# Ethernet2.net
KiCad netlist of a schematic drawn in Altium Designer
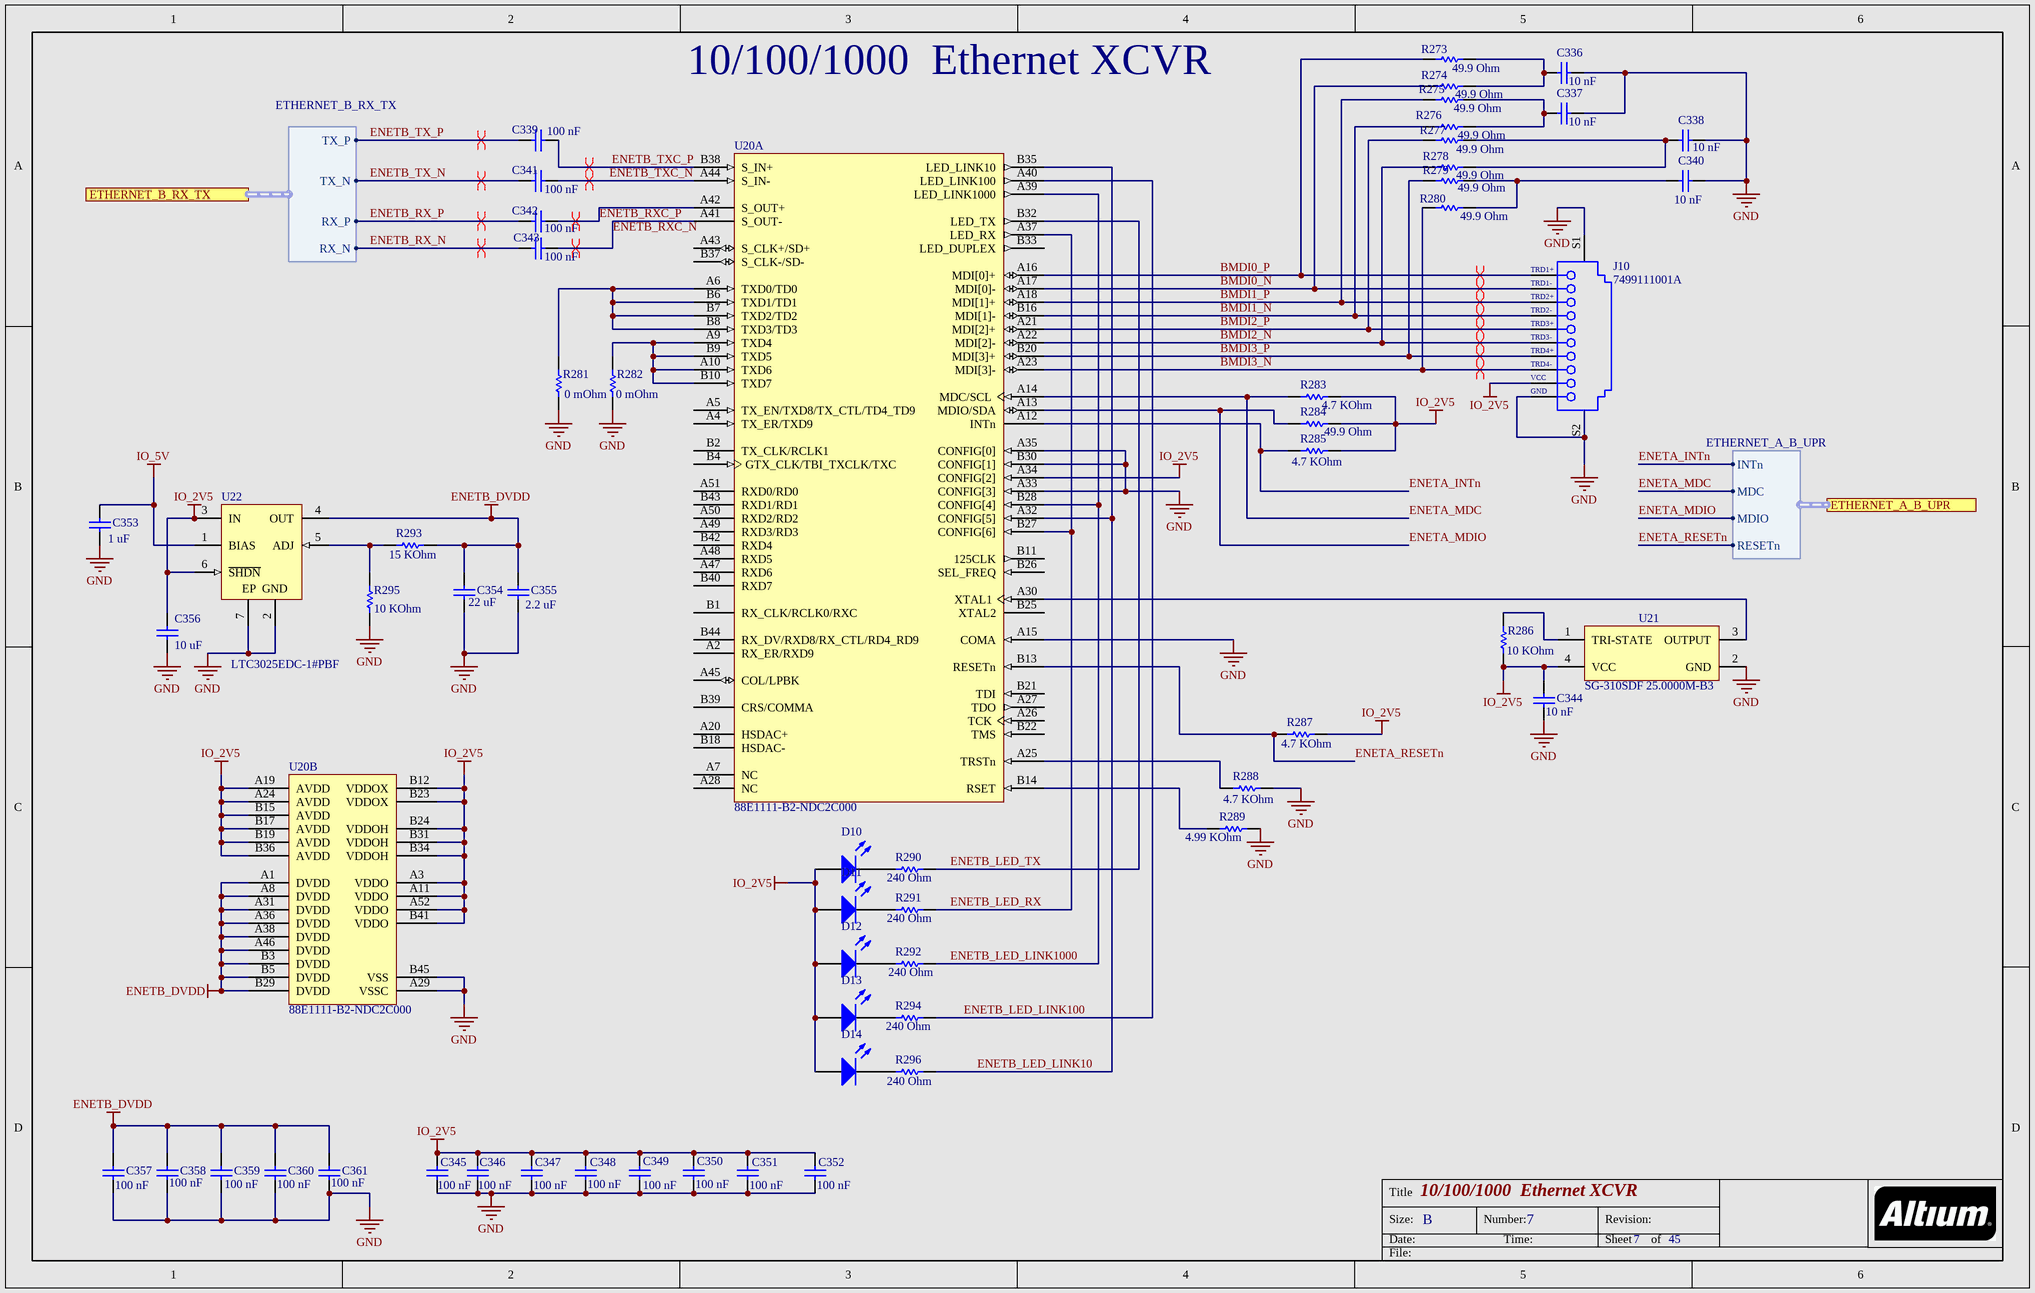
[diagram p0:  Ethernet2.SchDoc]

(export (version "E")
  (design (tool "Eeschema 10.0.6"))
  (components
    (comp (ref "C336")
      (value "GRM155R71H103KA88D")
      (footprint "CAPC1005X55X25ML05T10")
      (description "Chip Capacitor, 10 nF, +/- 10%, 50 V, -55 to 125 degC, 0402 (1005 Metric), RoHS, Tape and Reel")
      (fields
        (field (name "TOLERANCE") "10%")
        (field (name "CAPACITANCE") "10 nF")
        (field (name "MANUFACTURER") "Basic Passives")
      )
      (libsource (lib "Altium Content Vault") (part "CAP-NP-2"))
    )
    (comp (ref "C337")
      (value "GRM155R71H103KA88D")
      (footprint "CAPC1005X55X25ML05T10")
      (description "Chip Capacitor, 10 nF, +/- 10%, 50 V, -55 to 125 degC, 0402 (1005 Metric), RoHS, Tape and Reel")
      (fields
        (field (name "TOLERANCE") "10%")
        (field (name "CAPACITANCE") "10 nF")
        (field (name "MANUFACTURER") "Basic Passives")
      )
      (libsource (lib "Altium Content Vault") (part "CAP-NP-2"))
    )
    (comp (ref "C338")
      (value "GRM155R71H103KA88D")
      (footprint "CAPC1005X55X25ML05T10")
      (description "Chip Capacitor, 10 nF, +/- 10%, 50 V, -55 to 125 degC, 0402 (1005 Metric), RoHS, Tape and Reel")
      (fields
        (field (name "TOLERANCE") "10%")
        (field (name "CAPACITANCE") "10 nF")
        (field (name "MANUFACTURER") "Basic Passives")
      )
      (libsource (lib "Altium Content Vault") (part "CAP-NP-2"))
    )
    (comp (ref "C339")
      (value "C1005X7R1E104M")
      (footprint "CAPC1005X55X10LL05")
      (description "Chip Capacitor, 0.1 uF, +/- 20%, 25 V, -55 to 125 degC, 0402 (1005 Metric), RoHS, Tape and Reel")
      (fields (field (name "TOLERANCE") "20%") (field (name "CAPACITANCE") "100 nF"))
      (libsource (lib "Altium Content Vault") (part "CAP-NP-2"))
    )
    (comp (ref "C340")
      (value "GRM155R71H103KA88D")
      (footprint "CAPC1005X55X25ML05T10")
      (description "Chip Capacitor, 10 nF, +/- 10%, 50 V, -55 to 125 degC, 0402 (1005 Metric), RoHS, Tape and Reel")
      (fields
        (field (name "TOLERANCE") "10%")
        (field (name "CAPACITANCE") "10 nF")
        (field (name "MANUFACTURER") "Basic Passives")
      )
      (libsource (lib "Altium Content Vault") (part "CAP-NP-2"))
    )
    (comp (ref "C341")
      (value "C1005X7R1E104M")
      (footprint "CAPC1005X55X10LL05")
      (description "Chip Capacitor, 0.1 uF, +/- 20%, 25 V, -55 to 125 degC, 0402 (1005 Metric), RoHS, Tape and Reel")
      (fields (field (name "TOLERANCE") "20%") (field (name "CAPACITANCE") "100 nF"))
      (libsource (lib "Altium Content Vault") (part "CAP-NP-2"))
    )
    (comp (ref "C342")
      (value "C1005X7R1E104M")
      (footprint "CAPC1005X55X10LL05")
      (description "Chip Capacitor, 0.1 uF, +/- 20%, 25 V, -55 to 125 degC, 0402 (1005 Metric), RoHS, Tape and Reel")
      (fields (field (name "TOLERANCE") "20%") (field (name "CAPACITANCE") "100 nF"))
      (libsource (lib "Altium Content Vault") (part "CAP-NP-2"))
    )
    (comp (ref "C343")
      (value "C1005X7R1E104M")
      (footprint "CAPC1005X55X10LL05")
      (description "Chip Capacitor, 0.1 uF, +/- 20%, 25 V, -55 to 125 degC, 0402 (1005 Metric), RoHS, Tape and Reel")
      (fields (field (name "TOLERANCE") "20%") (field (name "CAPACITANCE") "100 nF"))
      (libsource (lib "Altium Content Vault") (part "CAP-NP-2"))
    )
    (comp (ref "C344")
      (value "GRM155R71H103KA88D")
      (footprint "CAPC1005X55X25ML05T10")
      (description "Chip Capacitor, 10 nF, +/- 10%, 50 V, -55 to 125 degC, 0402 (1005 Metric), RoHS, Tape and Reel")
      (fields
        (field (name "TOLERANCE") "10%")
        (field (name "CAPACITANCE") "10 nF")
        (field (name "MANUFACTURER") "Basic Passives")
      )
      (libsource (lib "Altium Content Vault") (part "CAP-NP-2"))
    )
    (comp (ref "C345")
      (value "C1005X7R1E104M")
      (footprint "CAPC1005X55X10LL05")
      (description "Chip Capacitor, 0.1 uF, +/- 20%, 25 V, -55 to 125 degC, 0402 (1005 Metric), RoHS, Tape and Reel")
      (fields (field (name "TOLERANCE") "20%") (field (name "CAPACITANCE") "100 nF"))
      (libsource (lib "Altium Content Vault") (part "CAP-NP-2"))
    )
    (comp (ref "C346")
      (value "C1005X7R1E104M")
      (footprint "CAPC1005X55X10LL05")
      (description "Chip Capacitor, 0.1 uF, +/- 20%, 25 V, -55 to 125 degC, 0402 (1005 Metric), RoHS, Tape and Reel")
      (fields (field (name "TOLERANCE") "20%") (field (name "CAPACITANCE") "100 nF"))
      (libsource (lib "Altium Content Vault") (part "CAP-NP-2"))
    )
    (comp (ref "C347")
      (value "C1005X7R1E104M")
      (footprint "CAPC1005X55X10LL05")
      (description "Chip Capacitor, 0.1 uF, +/- 20%, 25 V, -55 to 125 degC, 0402 (1005 Metric), RoHS, Tape and Reel")
      (fields (field (name "TOLERANCE") "20%") (field (name "CAPACITANCE") "100 nF"))
      (libsource (lib "Altium Content Vault") (part "CAP-NP-2"))
    )
    (comp (ref "C348")
      (value "C1005X7R1E104M")
      (footprint "CAPC1005X55X10LL05")
      (description "Chip Capacitor, 0.1 uF, +/- 20%, 25 V, -55 to 125 degC, 0402 (1005 Metric), RoHS, Tape and Reel")
      (fields (field (name "TOLERANCE") "20%") (field (name "CAPACITANCE") "100 nF"))
      (libsource (lib "Altium Content Vault") (part "CAP-NP-2"))
    )
    (comp (ref "C349")
      (value "C1005X7R1E104M")
      (footprint "CAPC1005X55X10LL05")
      (description "Chip Capacitor, 0.1 uF, +/- 20%, 25 V, -55 to 125 degC, 0402 (1005 Metric), RoHS, Tape and Reel")
      (fields (field (name "TOLERANCE") "20%") (field (name "CAPACITANCE") "100 nF"))
      (libsource (lib "Altium Content Vault") (part "CAP-NP-2"))
    )
    (comp (ref "C350")
      (value "C1005X7R1E104M")
      (footprint "CAPC1005X55X10LL05")
      (description "Chip Capacitor, 0.1 uF, +/- 20%, 25 V, -55 to 125 degC, 0402 (1005 Metric), RoHS, Tape and Reel")
      (fields (field (name "TOLERANCE") "20%") (field (name "CAPACITANCE") "100 nF"))
      (libsource (lib "Altium Content Vault") (part "CAP-NP-2"))
    )
    (comp (ref "C351")
      (value "C1005X7R1E104M")
      (footprint "CAPC1005X55X10LL05")
      (description "Chip Capacitor, 0.1 uF, +/- 20%, 25 V, -55 to 125 degC, 0402 (1005 Metric), RoHS, Tape and Reel")
      (fields (field (name "TOLERANCE") "20%") (field (name "CAPACITANCE") "100 nF"))
      (libsource (lib "Altium Content Vault") (part "CAP-NP-2"))
    )
    (comp (ref "C352")
      (value "C1005X7R1E104M")
      (footprint "CAPC1005X55X10LL05")
      (description "Chip Capacitor, 0.1 uF, +/- 20%, 25 V, -55 to 125 degC, 0402 (1005 Metric), RoHS, Tape and Reel")
      (fields (field (name "TOLERANCE") "20%") (field (name "CAPACITANCE") "100 nF"))
      (libsource (lib "Altium Content Vault") (part "CAP-NP-2"))
    )
    (comp (ref "C353")
      (value "CGB2A1X5R1E105K033BC")
      (footprint "CAPC1005X33X10LL5")
      (description "Chip Capacitor, 1 uF, +/- 10%, 25 V, -55 to 85 degC, 0402 (1005 Metric), RoHS, Tape and Reel")
      (fields (field (name "CAPACITANCE") "1 uF") (field (name "TOLERANCE") "10%"))
      (libsource (lib "") (part "CAP-NP-2_1"))
    )
    (comp (ref "C354")
      (value "GRM31CR61E226KE15L")
      (footprint "CAPC3216X180X55ML20T25")
      (description "Chip Capacitor, 22 uF, +/- 10%, 25 V, -55 to 85 degC, 1206 (3216 Metric), RoHS, Tape and Reel")
      (fields (field (name "TOLERANCE") "10%") (field (name "CAPACITANCE") "22 uF"))
      (libsource (lib "Altium Content Vault") (part "CAP-NP-2"))
    )
    (comp (ref "C355")
      (value "GRM188R61A225KE34x")
      (footprint "CAPC1608X90X35ML10T15")
      (description "Chip Capacitor, 2.2 uF, +/- 10%, 10 V, -55 to 85 degC, 0603 (1608 Metric), RoHS, Tape and Reel")
      (fields (field (name "TOLERANCE") "10%") (field (name "CAPACITANCE") "2.2 uF"))
      (libsource (lib "") (part "CAP-NP-2_1"))
    )
    (comp (ref "C356")
      (value "C2012X5R1C106K085AC")
      (footprint "CAPC2013X100X20NL20")
      (description "Chip Capacitor, 10 uF, +/- 10%, 16 V, -55 to 85 degC, 0805 (2012 Metric), RoHS, Tape and Reel")
      (fields (field (name "TOLERANCE") "10%") (field (name "CAPACITANCE") "10 uF"))
      (libsource (lib "") (part "CAP-NP-2_1"))
    )
    (comp (ref "C357")
      (value "C1005X7R1E104M")
      (footprint "CAPC1005X55X10LL05")
      (description "Chip Capacitor, 0.1 uF, +/- 20%, 25 V, -55 to 125 degC, 0402 (1005 Metric), RoHS, Tape and Reel")
      (fields (field (name "TOLERANCE") "20%") (field (name "CAPACITANCE") "100 nF"))
      (libsource (lib "Altium Content Vault") (part "CAP-NP-2"))
    )
    (comp (ref "C358")
      (value "C1005X7R1E104M")
      (footprint "CAPC1005X55X10LL05")
      (description "Chip Capacitor, 0.1 uF, +/- 20%, 25 V, -55 to 125 degC, 0402 (1005 Metric), RoHS, Tape and Reel")
      (fields (field (name "TOLERANCE") "20%") (field (name "CAPACITANCE") "100 nF"))
      (libsource (lib "Altium Content Vault") (part "CAP-NP-2"))
    )
    (comp (ref "C359")
      (value "C1005X7R1E104M")
      (footprint "CAPC1005X55X10LL05")
      (description "Chip Capacitor, 0.1 uF, +/- 20%, 25 V, -55 to 125 degC, 0402 (1005 Metric), RoHS, Tape and Reel")
      (fields (field (name "TOLERANCE") "20%") (field (name "CAPACITANCE") "100 nF"))
      (libsource (lib "Altium Content Vault") (part "CAP-NP-2"))
    )
    (comp (ref "C360")
      (value "C1005X7R1E104M")
      (footprint "CAPC1005X55X10LL05")
      (description "Chip Capacitor, 0.1 uF, +/- 20%, 25 V, -55 to 125 degC, 0402 (1005 Metric), RoHS, Tape and Reel")
      (fields (field (name "TOLERANCE") "20%") (field (name "CAPACITANCE") "100 nF"))
      (libsource (lib "Altium Content Vault") (part "CAP-NP-2"))
    )
    (comp (ref "C361")
      (value "C1005X7R1E104M")
      (footprint "CAPC1005X55X10LL05")
      (description "Chip Capacitor, 0.1 uF, +/- 20%, 25 V, -55 to 125 degC, 0402 (1005 Metric), RoHS, Tape and Reel")
      (fields (field (name "TOLERANCE") "20%") (field (name "CAPACITANCE") "100 nF"))
      (libsource (lib "Altium Content Vault") (part "CAP-NP-2"))
    )
    (comp (ref "D10")
      (value "150060VS75000")
      (footprint "0603_A")
      (description "SMD mono-color Chip LED, WL-SMCW, Bright Green")
      (fields (field (name "MANUFACTURER") "Wuerth Elektronik"))
      (libsource (lib "Altium Content Vault") (part "CMP-1426-00006-1"))
    )
    (comp (ref "D11")
      (value "150060VS75000")
      (footprint "0603_A")
      (description "SMD mono-color Chip LED, WL-SMCW, Bright Green")
      (fields (field (name "MANUFACTURER") "Wuerth Elektronik"))
      (libsource (lib "Altium Content Vault") (part "CMP-1426-00006-1"))
    )
    (comp (ref "D12")
      (value "150060VS75000")
      (footprint "0603_A")
      (description "SMD mono-color Chip LED, WL-SMCW, Bright Green")
      (fields (field (name "MANUFACTURER") "Wuerth Elektronik"))
      (libsource (lib "Altium Content Vault") (part "CMP-1426-00006-1"))
    )
    (comp (ref "D13")
      (value "150060VS75000")
      (footprint "0603_A")
      (description "SMD mono-color Chip LED, WL-SMCW, Bright Green")
      (fields (field (name "MANUFACTURER") "Wuerth Elektronik"))
      (libsource (lib "Altium Content Vault") (part "CMP-1426-00006-1"))
    )
    (comp (ref "D14")
      (value "150060VS75000")
      (footprint "0603_A")
      (description "SMD mono-color Chip LED, WL-SMCW, Bright Green")
      (fields (field (name "MANUFACTURER") "Wuerth Elektronik"))
      (libsource (lib "Altium Content Vault") (part "CMP-1426-00006-1"))
    )
    (comp (ref "J10")
      (value "7499111001A")
      (footprint "WE-7499111001A_V")
      (description "RJ45 LAN Transformer, Modular JACK, 0 to 70 degC, 10-Pin THD, RoHS, Tube")
      (libsource (lib "Altium Content Vault") (part "RJ45-10-2SHLD_A"))
    )
    (comp (ref "R273")
      (value "NRC04F49R9TRF")
      (footprint "RESC1005X35X25NL8T10")
      (description "Chip Resistor, 49.9 Ohm, +/- 1%, 0.06 W, -55 to 155 degC, 0402 (1005 Metric), RoHS, Tape and Reel")
      (fields (field (name "TOLERANCE") "1%") (field (name "RESISTANCE") "49.9 Ohm"))
      (libsource (lib "Altium Content Vault") (part "CMP-1599-00001-2"))
    )
    (comp (ref "R274")
      (value "NRC04F49R9TRF")
      (footprint "RESC1005X35X25NL8T10")
      (description "Chip Resistor, 49.9 Ohm, +/- 1%, 0.06 W, -55 to 155 degC, 0402 (1005 Metric), RoHS, Tape and Reel")
      (fields (field (name "TOLERANCE") "1%") (field (name "RESISTANCE") "49.9 Ohm"))
      (libsource (lib "Altium Content Vault") (part "RES-2"))
    )
    (comp (ref "R275")
      (value "NRC04F49R9TRF")
      (footprint "RESC1005X35X25NL8T10")
      (description "Chip Resistor, 49.9 Ohm, +/- 1%, 0.06 W, -55 to 155 degC, 0402 (1005 Metric), RoHS, Tape and Reel")
      (fields (field (name "TOLERANCE") "1%") (field (name "RESISTANCE") "49.9 Ohm"))
      (libsource (lib "Altium Content Vault") (part "RES-2"))
    )
    (comp (ref "R276")
      (value "NRC04F49R9TRF")
      (footprint "RESC1005X35X25NL8T10")
      (description "Chip Resistor, 49.9 Ohm, +/- 1%, 0.06 W, -55 to 155 degC, 0402 (1005 Metric), RoHS, Tape and Reel")
      (fields (field (name "TOLERANCE") "1%") (field (name "RESISTANCE") "49.9 Ohm"))
      (libsource (lib "Altium Content Vault") (part "CMP-1599-00001-2"))
    )
    (comp (ref "R277")
      (value "NRC04F49R9TRF")
      (footprint "RESC1005X35X25NL8T10")
      (description "Chip Resistor, 49.9 Ohm, +/- 1%, 0.06 W, -55 to 155 degC, 0402 (1005 Metric), RoHS, Tape and Reel")
      (fields (field (name "TOLERANCE") "1%") (field (name "RESISTANCE") "49.9 Ohm"))
      (libsource (lib "Altium Content Vault") (part "RES-2"))
    )
    (comp (ref "R278")
      (value "NRC04F49R9TRF")
      (footprint "RESC1005X35X25NL8T10")
      (description "Chip Resistor, 49.9 Ohm, +/- 1%, 0.06 W, -55 to 155 degC, 0402 (1005 Metric), RoHS, Tape and Reel")
      (fields (field (name "TOLERANCE") "1%") (field (name "RESISTANCE") "49.9 Ohm"))
      (libsource (lib "Altium Content Vault") (part "RES-2"))
    )
    (comp (ref "R279")
      (value "NRC04F49R9TRF")
      (footprint "RESC1005X35X25NL8T10")
      (description "Chip Resistor, 49.9 Ohm, +/- 1%, 0.06 W, -55 to 155 degC, 0402 (1005 Metric), RoHS, Tape and Reel")
      (fields (field (name "TOLERANCE") "1%") (field (name "RESISTANCE") "49.9 Ohm"))
      (libsource (lib "Altium Content Vault") (part "CMP-1599-00001-2"))
    )
    (comp (ref "R280")
      (value "NRC04F49R9TRF")
      (footprint "RESC1005X35X25NL8T10")
      (description "Chip Resistor, 49.9 Ohm, +/- 1%, 0.06 W, -55 to 155 degC, 0402 (1005 Metric), RoHS, Tape and Reel")
      (fields (field (name "TOLERANCE") "1%") (field (name "RESISTANCE") "49.9 Ohm"))
      (libsource (lib "Altium Content Vault") (part "RES-2"))
    )
    (comp (ref "R281")
      (value "ERJ-2GE0R00X")
      (footprint "RESC1005X40X25ML05T05")
      (description "Chip Resistor, 0 mOhm, +/- 5%, 100 mW, -55 to 155 degC, 0402 (1005 Metric), RoHS, Tape and Reel")
      (fields
        (field (name "TOLERANCE") "5%")
        (field (name "RESISTANCE") "0 mOhm")
        (field (name "MANUFACTURER") "Basic Passives")
      )
      (libsource (lib "Altium Content Vault") (part "RES-2"))
    )
    (comp (ref "R282")
      (value "ERJ-2GE0R00X")
      (footprint "RESC1005X40X25ML05T05")
      (description "Chip Resistor, 0 mOhm, +/- 5%, 100 mW, -55 to 155 degC, 0402 (1005 Metric), RoHS, Tape and Reel")
      (fields
        (field (name "TOLERANCE") "5%")
        (field (name "RESISTANCE") "0 mOhm")
        (field (name "MANUFACTURER") "Basic Passives")
      )
      (libsource (lib "Altium Content Vault") (part "RES-2"))
    )
    (comp (ref "R283")
      (value "ERJ-2RKF4701X")
      (footprint "RESC1005X40X25LL05T05")
      (description "Chip Resistor, 4.7 KOhm, +/- 1%, 0.1 W, -55 to 155 degC, 0402 (1005 Metric), RoHS, Tape and Reel")
      (fields (field (name "TOLERANCE") "1%") (field (name "RESISTANCE") "4.7 KOhm"))
      (libsource (lib "Altium Content Vault") (part "RES-2"))
    )
    (comp (ref "R284")
      (value "NRC04F49R9TRF")
      (footprint "RESC1005X35X25NL8T10")
      (description "Chip Resistor, 49.9 Ohm, +/- 1%, 0.06 W, -55 to 155 degC, 0402 (1005 Metric), RoHS, Tape and Reel")
      (fields (field (name "TOLERANCE") "1%") (field (name "RESISTANCE") "49.9 Ohm"))
      (libsource (lib "Altium Content Vault") (part "CMP-1599-00001-2"))
    )
    (comp (ref "R285")
      (value "ERJ-2RKF4701X")
      (footprint "RESC1005X40X25LL05T05")
      (description "Chip Resistor, 4.7 KOhm, +/- 1%, 0.1 W, -55 to 155 degC, 0402 (1005 Metric), RoHS, Tape and Reel")
      (fields (field (name "TOLERANCE") "1%") (field (name "RESISTANCE") "4.7 KOhm"))
      (libsource (lib "Altium Content Vault") (part "RES-2"))
    )
    (comp (ref "R286")
      (value "ERJ-2RKF1002X")
      (footprint "RESC1005X40X25NL05T05")
      (description "Chip Resistor, 10 KOhm, +/- 1%, 100 mW, -55 to 155 degC, 0402 (1005 Metric), RoHS, Tape and Reel")
      (fields
        (field (name "TOLERANCE") "1%")
        (field (name "RESISTANCE") "10 KOhm")
        (field (name "MANUFACTURER") "Basic Passives")
      )
      (libsource (lib "Altium Content Vault") (part "RES-2"))
    )
    (comp (ref "R287")
      (value "ERJ-2RKF4701X")
      (footprint "RESC1005X40X25LL05T05")
      (description "Chip Resistor, 4.7 KOhm, +/- 1%, 0.1 W, -55 to 155 degC, 0402 (1005 Metric), RoHS, Tape and Reel")
      (fields (field (name "TOLERANCE") "1%") (field (name "RESISTANCE") "4.7 KOhm"))
      (libsource (lib "Altium Content Vault") (part "RES-2"))
    )
    (comp (ref "R288")
      (value "ERJ-2RKF4701X")
      (footprint "RESC1005X40X25LL05T05")
      (description "Chip Resistor, 4.7 KOhm, +/- 1%, 0.1 W, -55 to 155 degC, 0402 (1005 Metric), RoHS, Tape and Reel")
      (fields (field (name "TOLERANCE") "1%") (field (name "RESISTANCE") "4.7 KOhm"))
      (libsource (lib "Altium Content Vault") (part "RES-2"))
    )
    (comp (ref "R289")
      (value "ERJ-2RKF4991X")
      (footprint "RESC1005X40X25NL05T05")
      (description "Chip Resistor, 4.99 KOhm, +/- 1%, 100 mW, -55 to 155 degC, 0402 (1005 Metric), RoHS, Tape and Reel")
      (fields
        (field (name "TOLERANCE") "1%")
        (field (name "RESISTANCE") "4.99 KOhm")
        (field (name "MANUFACTURER") "Basic Passives")
      )
      (libsource (lib "Altium Content Vault") (part "RES-2"))
    )
    (comp (ref "R290")
      (value "ERJ-2RKF2400X")
      (footprint "RESC1005X40X25NL05T05")
      (description "Chip Resistor, 240 Ohm, +/- 1%, 100 mW, -55 to 155 degC, 0402 (1005 Metric), RoHS, Tape and Reel")
      (fields (field (name "TOLERANCE") "1%") (field (name "RESISTANCE") "240 Ohm"))
      (libsource (lib "Altium Content Vault") (part "RES-2"))
    )
    (comp (ref "R291")
      (value "ERJ-2RKF2400X")
      (footprint "RESC1005X40X25NL05T05")
      (description "Chip Resistor, 240 Ohm, +/- 1%, 100 mW, -55 to 155 degC, 0402 (1005 Metric), RoHS, Tape and Reel")
      (fields (field (name "TOLERANCE") "1%") (field (name "RESISTANCE") "240 Ohm"))
      (libsource (lib "Altium Content Vault") (part "RES-2"))
    )
    (comp (ref "R292")
      (value "ERJ-2RKF2400X")
      (footprint "RESC1005X40X25NL05T05")
      (description "Chip Resistor, 240 Ohm, +/- 1%, 100 mW, -55 to 155 degC, 0402 (1005 Metric), RoHS, Tape and Reel")
      (fields (field (name "TOLERANCE") "1%") (field (name "RESISTANCE") "240 Ohm"))
      (libsource (lib "Altium Content Vault") (part "RES-2"))
    )
    (comp (ref "R293")
      (value "ERJ-2RKF1502X")
      (footprint "RESC1005X40X25ML05T05")
      (description "Chip Resistor, 15 KOhm, +/- 1%, 100 mW, -55 to 155 degC, 0402 (1005 Metric), RoHS, Tape and Reel")
      (fields
        (field (name "RESISTANCE") "15 KOhm")
        (field (name "TOLERANCE") "1%")
        (field (name "MANUFACTURER") "Basic Passives")
      )
      (libsource (lib "Altium Content Vault") (part "RES-2"))
    )
    (comp (ref "R294")
      (value "ERJ-2RKF2400X")
      (footprint "RESC1005X40X25NL05T05")
      (description "Chip Resistor, 240 Ohm, +/- 1%, 100 mW, -55 to 155 degC, 0402 (1005 Metric), RoHS, Tape and Reel")
      (fields (field (name "TOLERANCE") "1%") (field (name "RESISTANCE") "240 Ohm"))
      (libsource (lib "Altium Content Vault") (part "RES-2"))
    )
    (comp (ref "R295")
      (value "ERJ-2RKF1002X")
      (footprint "RESC1005X40X25NL05T05")
      (description "Chip Resistor, 10 KOhm, +/- 1%, 100 mW, -55 to 155 degC, 0402 (1005 Metric), RoHS, Tape and Reel")
      (fields
        (field (name "TOLERANCE") "1%")
        (field (name "RESISTANCE") "10 KOhm")
        (field (name "MANUFACTURER") "Basic Passives")
      )
      (libsource (lib "Altium Content Vault") (part "RES-2"))
    )
    (comp (ref "R296")
      (value "ERJ-2RKF2400X")
      (footprint "RESC1005X40X25NL05T05")
      (description "Chip Resistor, 240 Ohm, +/- 1%, 100 mW, -55 to 155 degC, 0402 (1005 Metric), RoHS, Tape and Reel")
      (fields (field (name "TOLERANCE") "1%") (field (name "RESISTANCE") "240 Ohm"))
      (libsource (lib "Altium Content Vault") (part "RES-2"))
    )
    (comp (ref "U20")
      (value "88E1111-B2-NDC2C000")
      (footprint "MARV-NDC96")
      (description "Integrated 10/100/1000 Ultra Gigabit Ethernet Transceiver, Commercial Grade, 96-Pin QFN, RoHS")
      (libsource (lib "Altium Content Vault") (part "MARV-88E1111-NDC96"))
    )
    (comp (ref "U21")
      (value "SG-310SDF 25.0000M-B3")
      (footprint "EPSON-SG-310-4_V")
      (description "Crystal Oscillator (SPXO), 2.5 V, 25 MHz, -20 to 70 degC, 4-Pin SMD, RoHS, Tape and Reel")
      (libsource (lib "Altium Content Vault") (part "XTAL-1-3-4_B"))
    )
    (comp (ref "U22")
      (value "LTC3025EDC-1#PBF")
      (footprint "LT-DC6-6_V")
      (fields (field (name "MANUFACTURER") "Linear Technology"))
      (libsource (lib "Altium Content Vault") (part "LT-LTC302-DC6-6"))
    )
  )
  (nets
    (net (code "3") (name "/BMDI0_N") (class "Default")
      (node (ref "J10") (pin "2") (pinfunction "TRD1-_2") (pintype "passive"))
      (node (ref "R274") (pin "1") (pinfunction "1_1") (pintype "passive"))
      (node (ref "U20") (pin "A17") (pinfunction "MDI[0]-_A17") (pintype "bidirectional"))
    )
    (net (code "4") (name "/BMDI0_P") (class "Default")
      (node (ref "J10") (pin "1") (pinfunction "TRD1+_1") (pintype "passive"))
      (node (ref "R273") (pin "1") (pinfunction "1_1") (pintype "passive"))
      (node (ref "U20") (pin "A16") (pinfunction "MDI[0]+_A16") (pintype "bidirectional"))
    )
    (net (code "5") (name "/BMDI1_N") (class "Default")
      (node (ref "J10") (pin "4") (pinfunction "TRD2-_4") (pintype "passive"))
      (node (ref "R276") (pin "1") (pinfunction "1_1") (pintype "passive"))
      (node (ref "U20") (pin "B16") (pinfunction "MDI[1]-_B16") (pintype "bidirectional"))
    )
    (net (code "6") (name "/BMDI1_P") (class "Default")
      (node (ref "J10") (pin "3") (pinfunction "TRD2+_3") (pintype "passive"))
      (node (ref "R275") (pin "1") (pinfunction "1_1") (pintype "passive"))
      (node (ref "U20") (pin "A18") (pinfunction "MDI[1]+_A18") (pintype "bidirectional"))
    )
    (net (code "7") (name "/BMDI2_N") (class "Default")
      (node (ref "J10") (pin "6") (pinfunction "TRD3-_6") (pintype "passive"))
      (node (ref "R278") (pin "1") (pinfunction "1_1") (pintype "passive"))
      (node (ref "U20") (pin "A22") (pinfunction "MDI[2]-_A22") (pintype "bidirectional"))
    )
    (net (code "8") (name "/BMDI2_P") (class "Default")
      (node (ref "J10") (pin "5") (pinfunction "TRD3+_5") (pintype "passive"))
      (node (ref "R277") (pin "1") (pinfunction "1_1") (pintype "passive"))
      (node (ref "U20") (pin "A21") (pinfunction "MDI[2]+_A21") (pintype "bidirectional"))
    )
    (net (code "9") (name "/BMDI3_N") (class "Default")
      (node (ref "J10") (pin "8") (pinfunction "TRD4-_8") (pintype "passive"))
      (node (ref "R280") (pin "1") (pinfunction "1_1") (pintype "passive"))
      (node (ref "U20") (pin "A23") (pinfunction "MDI[3]-_A23") (pintype "bidirectional"))
    )
    (net (code "10") (name "/BMDI3_P") (class "Default")
      (node (ref "J10") (pin "7") (pinfunction "TRD4+_7") (pintype "passive"))
      (node (ref "R279") (pin "1") (pinfunction "1_1") (pintype "passive"))
      (node (ref "U20") (pin "B20") (pinfunction "MDI[3]+_B20") (pintype "bidirectional"))
    )
    (net (code "11") (name "/ENETA_INTn") (class "Default")
      (node (ref "R285") (pin "1") (pinfunction "1_1") (pintype "passive"))
      (node (ref "U20") (pin "A12") (pinfunction "INTn_A12") (pintype "passive"))
    )
    (net (code "12") (name "/ENETA_MDC") (class "Default")
      (node (ref "R283") (pin "1") (pinfunction "1_1") (pintype "passive"))
      (node (ref "U20") (pin "A14") (pinfunction "MDC/SCL_A14") (pintype "input"))
    )
    (net (code "13") (name "/ENETA_MDIO") (class "Default")
      (node (ref "R284") (pin "1") (pinfunction "1_1") (pintype "passive"))
      (node (ref "U20") (pin "A13") (pinfunction "MDIO/SDA_A13") (pintype "bidirectional"))
    )
    (net (code "14") (name "/ENETA_RESETn") (class "Default")
      (node (ref "R287") (pin "1") (pinfunction "1_1") (pintype "passive"))
      (node (ref "U20") (pin "B13") (pinfunction "RESETn_B13") (pintype "input"))
    )
    (net (code "15") (name "/ENETB_LED_LINK10") (class "Default")
      (node (ref "R296") (pin "2") (pinfunction "2_2") (pintype "passive"))
      (node (ref "U20") (pin "A32") (pinfunction "CONFIG[5]_A32") (pintype "input"))
      (node (ref "U20") (pin "B35") (pinfunction "LED_LINK10_B35") (pintype "output"))
    )
    (net (code "16") (name "/ENETB_LED_LINK100") (class "Default")
      (node (ref "R294") (pin "2") (pinfunction "2_2") (pintype "passive"))
      (node (ref "U20") (pin "A40") (pinfunction "LED_LINK100_A40") (pintype "output"))
    )
    (net (code "17") (name "/ENETB_LED_LINK1000") (class "Default")
      (node (ref "R292") (pin "2") (pinfunction "2_2") (pintype "passive"))
      (node (ref "U20") (pin "A39") (pinfunction "LED_LINK1000_A39") (pintype "output"))
      (node (ref "U20") (pin "B28") (pinfunction "CONFIG[4]_B28") (pintype "input"))
    )
    (net (code "18") (name "/ENETB_LED_RX") (class "Default")
      (node (ref "R291") (pin "2") (pinfunction "2_2") (pintype "passive"))
      (node (ref "U20") (pin "A37") (pinfunction "LED_RX_A37") (pintype "output"))
      (node (ref "U20") (pin "B27") (pinfunction "CONFIG[6]_B27") (pintype "input"))
    )
    (net (code "19") (name "/ENETB_LED_TX") (class "Default")
      (node (ref "R290") (pin "2") (pinfunction "2_2") (pintype "passive"))
      (node (ref "U20") (pin "B32") (pinfunction "LED_TX_B32") (pintype "output"))
    )
    (net (code "20") (name "/ENETB_RXC_N") (class "Default")
      (node (ref "C343") (pin "2") (pinfunction "2_2") (pintype "passive"))
      (node (ref "U20") (pin "A41") (pinfunction "S_OUT-_A41") (pintype "tri_state"))
    )
    (net (code "21") (name "/ENETB_RXC_P") (class "Default")
      (node (ref "C342") (pin "2") (pinfunction "2_2") (pintype "passive"))
      (node (ref "U20") (pin "A42") (pinfunction "S_OUT+_A42") (pintype "tri_state"))
    )
    (net (code "22") (name "/ENETB_RX_N") (class "Default")
      (node (ref "C343") (pin "1") (pinfunction "1_1") (pintype "passive"))
    )
    (net (code "23") (name "/ENETB_RX_P") (class "Default")
      (node (ref "C342") (pin "1") (pinfunction "1_1") (pintype "passive"))
    )
    (net (code "24") (name "/ENETB_TXC_N") (class "Default")
      (node (ref "C341") (pin "2") (pinfunction "2_2") (pintype "passive"))
      (node (ref "U20") (pin "A44") (pinfunction "S_IN-_A44") (pintype "input"))
    )
    (net (code "25") (name "/ENETB_TXC_P") (class "Default")
      (node (ref "C339") (pin "2") (pinfunction "2_2") (pintype "passive"))
      (node (ref "U20") (pin "B38") (pinfunction "S_IN+_B38") (pintype "input"))
    )
    (net (code "26") (name "/ENETB_TX_N") (class "Default")
      (node (ref "C341") (pin "1") (pinfunction "1_1") (pintype "passive"))
    )
    (net (code "27") (name "/ENETB_TX_P") (class "Default")
      (node (ref "C339") (pin "1") (pinfunction "1_1") (pintype "passive"))
    )
    (net (code "30") (name "ENETB_DVDD") (class "Default")
      (node (ref "C354") (pin "2") (pinfunction "2_2") (pintype "passive"))
      (node (ref "C355") (pin "2") (pinfunction "2_2") (pintype "passive"))
      (node (ref "C357") (pin "2") (pinfunction "2_2") (pintype "passive"))
      (node (ref "C358") (pin "2") (pinfunction "2_2") (pintype "passive"))
      (node (ref "C359") (pin "2") (pinfunction "2_2") (pintype "passive"))
      (node (ref "C360") (pin "2") (pinfunction "2_2") (pintype "passive"))
      (node (ref "C361") (pin "2") (pinfunction "2_2") (pintype "passive"))
      (node (ref "R293") (pin "2") (pinfunction "2_2") (pintype "passive"))
      (node (ref "U20") (pin "A1") (pinfunction "DVDD_A1") (pintype "power_in"))
      (node (ref "U20") (pin "A31") (pinfunction "DVDD_A31") (pintype "power_in"))
      (node (ref "U20") (pin "A36") (pinfunction "DVDD_A36") (pintype "power_in"))
      (node (ref "U20") (pin "A38") (pinfunction "DVDD_A38") (pintype "power_in"))
      (node (ref "U20") (pin "A46") (pinfunction "DVDD_A46") (pintype "power_in"))
      (node (ref "U20") (pin "A8") (pinfunction "DVDD_A8") (pintype "power_in"))
      (node (ref "U20") (pin "B29") (pinfunction "DVDD_B29") (pintype "power_in"))
      (node (ref "U20") (pin "B3") (pinfunction "DVDD_B3") (pintype "power_in"))
      (node (ref "U20") (pin "B5") (pinfunction "DVDD_B5") (pintype "power_in"))
      (node (ref "U22") (pin "4") (pinfunction "OUT_4") (pintype "power_in"))
    )
    (net (code "31") (name "GND") (class "Default")
      (node (ref "C336") (pin "2") (pinfunction "2_2") (pintype "passive"))
      (node (ref "C337") (pin "2") (pinfunction "2_2") (pintype "passive"))
      (node (ref "C338") (pin "2") (pinfunction "2_2") (pintype "passive"))
      (node (ref "C340") (pin "2") (pinfunction "2_2") (pintype "passive"))
      (node (ref "C344") (pin "1") (pinfunction "1_1") (pintype "passive"))
      (node (ref "C345") (pin "1") (pinfunction "1_1") (pintype "passive"))
      (node (ref "C346") (pin "1") (pinfunction "1_1") (pintype "passive"))
      (node (ref "C347") (pin "1") (pinfunction "1_1") (pintype "passive"))
      (node (ref "C348") (pin "1") (pinfunction "1_1") (pintype "passive"))
      (node (ref "C349") (pin "1") (pinfunction "1_1") (pintype "passive"))
      (node (ref "C350") (pin "1") (pinfunction "1_1") (pintype "passive"))
      (node (ref "C351") (pin "1") (pinfunction "1_1") (pintype "passive"))
      (node (ref "C352") (pin "1") (pinfunction "1_1") (pintype "passive"))
      (node (ref "C353") (pin "1") (pinfunction "1_1") (pintype "passive"))
      (node (ref "C354") (pin "1") (pinfunction "1_1") (pintype "passive"))
      (node (ref "C355") (pin "1") (pinfunction "1_1") (pintype "passive"))
      (node (ref "C356") (pin "1") (pinfunction "1_1") (pintype "passive"))
      (node (ref "C357") (pin "1") (pinfunction "1_1") (pintype "passive"))
      (node (ref "C358") (pin "1") (pinfunction "1_1") (pintype "passive"))
      (node (ref "C359") (pin "1") (pinfunction "1_1") (pintype "passive"))
      (node (ref "C360") (pin "1") (pinfunction "1_1") (pintype "passive"))
      (node (ref "C361") (pin "1") (pinfunction "1_1") (pintype "passive"))
      (node (ref "J10") (pin "10") (pinfunction "GND_10") (pintype "power_in"))
      (node (ref "J10") (pin "S1") (pinfunction "SHLD_S1") (pintype "passive"))
      (node (ref "J10") (pin "S2") (pinfunction "SHLD_S2") (pintype "passive"))
      (node (ref "R281") (pin "1") (pinfunction "1_1") (pintype "passive"))
      (node (ref "R282") (pin "1") (pinfunction "1_1") (pintype "passive"))
      (node (ref "R288") (pin "2") (pinfunction "2_2") (pintype "passive"))
      (node (ref "R289") (pin "2") (pinfunction "2_2") (pintype "passive"))
      (node (ref "R295") (pin "1") (pinfunction "1_1") (pintype "passive"))
      (node (ref "U20") (pin "A15") (pinfunction "COMA_A15") (pintype "input"))
      (node (ref "U20") (pin "A29") (pinfunction "VSSC_A29") (pintype "power_in"))
      (node (ref "U20") (pin "A33") (pinfunction "CONFIG[3]_A33") (pintype "input"))
      (node (ref "U20") (pin "A35") (pinfunction "CONFIG[0]_A35") (pintype "input"))
      (node (ref "U20") (pin "B30") (pinfunction "CONFIG[1]_B30") (pintype "input"))
      (node (ref "U20") (pin "B45") (pinfunction "VSS_B45") (pintype "power_in"))
      (node (ref "U21") (pin "2") (pinfunction "GND_2") (pintype "power_in"))
      (node (ref "U22") (pin "2") (pinfunction "GND_2") (pintype "power_in"))
      (node (ref "U22") (pin "7") (pinfunction "EP_7") (pintype "power_in"))
    )
    (net (code "32") (name "IO_2V5") (class "Default")
      (node (ref "C344") (pin "2") (pinfunction "2_2") (pintype "passive"))
      (node (ref "C345") (pin "2") (pinfunction "2_2") (pintype "passive"))
      (node (ref "C346") (pin "2") (pinfunction "2_2") (pintype "passive"))
      (node (ref "C347") (pin "2") (pinfunction "2_2") (pintype "passive"))
      (node (ref "C348") (pin "2") (pinfunction "2_2") (pintype "passive"))
      (node (ref "C349") (pin "2") (pinfunction "2_2") (pintype "passive"))
      (node (ref "C350") (pin "2") (pinfunction "2_2") (pintype "passive"))
      (node (ref "C351") (pin "2") (pinfunction "2_2") (pintype "passive"))
      (node (ref "C352") (pin "2") (pinfunction "2_2") (pintype "passive"))
      (node (ref "C356") (pin "2") (pinfunction "2_2") (pintype "passive"))
      (node (ref "D10") (pin "2") (pinfunction "A_2") (pintype "passive"))
      (node (ref "D11") (pin "2") (pinfunction "A_2") (pintype "passive"))
      (node (ref "D12") (pin "2") (pinfunction "A_2") (pintype "passive"))
      (node (ref "D13") (pin "2") (pinfunction "A_2") (pintype "passive"))
      (node (ref "D14") (pin "2") (pinfunction "A_2") (pintype "passive"))
      (node (ref "J10") (pin "9") (pinfunction "VCC_9") (pintype "power_in"))
      (node (ref "R283") (pin "2") (pinfunction "2_2") (pintype "passive"))
      (node (ref "R284") (pin "2") (pinfunction "2_2") (pintype "passive"))
      (node (ref "R285") (pin "2") (pinfunction "2_2") (pintype "passive"))
      (node (ref "R286") (pin "1") (pinfunction "1_1") (pintype "passive"))
      (node (ref "R287") (pin "2") (pinfunction "2_2") (pintype "passive"))
      (node (ref "U20") (pin "A11") (pinfunction "VDDO_A11") (pintype "power_in"))
      (node (ref "U20") (pin "A19") (pinfunction "AVDD_A19") (pintype "power_in"))
      (node (ref "U20") (pin "A24") (pinfunction "AVDD_A24") (pintype "power_in"))
      (node (ref "U20") (pin "A3") (pinfunction "VDDO_A3") (pintype "power_in"))
      (node (ref "U20") (pin "A34") (pinfunction "CONFIG[2]_A34") (pintype "input"))
      (node (ref "U20") (pin "A52") (pinfunction "VDDO_A52") (pintype "power_in"))
      (node (ref "U20") (pin "B12") (pinfunction "VDDOX_B12") (pintype "power_in"))
      (node (ref "U20") (pin "B15") (pinfunction "AVDD_B15") (pintype "power_in"))
      (node (ref "U20") (pin "B17") (pinfunction "AVDD_B17") (pintype "power_in"))
      (node (ref "U20") (pin "B19") (pinfunction "AVDD_B19") (pintype "power_in"))
      (node (ref "U20") (pin "B23") (pinfunction "VDDOX_B23") (pintype "power_in"))
      (node (ref "U20") (pin "B24") (pinfunction "VDDOH_B24") (pintype "power_in"))
      (node (ref "U20") (pin "B31") (pinfunction "VDDOH_B31") (pintype "power_in"))
      (node (ref "U20") (pin "B34") (pinfunction "VDDOH_B34") (pintype "power_in"))
      (node (ref "U20") (pin "B36") (pinfunction "AVDD_B36") (pintype "power_in"))
      (node (ref "U20") (pin "B41") (pinfunction "VDDO_B41") (pintype "power_in"))
      (node (ref "U21") (pin "4") (pinfunction "VCC_4") (pintype "power_in"))
      (node (ref "U22") (pin "3") (pinfunction "IN_3") (pintype "power_in"))
      (node (ref "U22") (pin "6") (pinfunction "~{SHDN}_6") (pintype "input"))
    )
    (net (code "33") (name "IO_5V") (class "Default")
      (node (ref "C353") (pin "2") (pinfunction "2_2") (pintype "passive"))
      (node (ref "U22") (pin "1") (pinfunction "BIAS_1") (pintype "power_in"))
    )
    (net (code "34") (name "Net-(C336-Pad1)") (class "Default")
      (node (ref "C336") (pin "1") (pinfunction "1_1") (pintype "passive"))
      (node (ref "R273") (pin "2") (pinfunction "2_2") (pintype "passive"))
      (node (ref "R274") (pin "2") (pinfunction "2_2") (pintype "passive"))
    )
    (net (code "35") (name "Net-(C337-Pad1)") (class "Default")
      (node (ref "C337") (pin "1") (pinfunction "1_1") (pintype "passive"))
      (node (ref "R275") (pin "2") (pinfunction "2_2") (pintype "passive"))
      (node (ref "R276") (pin "2") (pinfunction "2_2") (pintype "passive"))
    )
    (net (code "36") (name "Net-(C338-Pad1)") (class "Default")
      (node (ref "C338") (pin "1") (pinfunction "1_1") (pintype "passive"))
      (node (ref "R277") (pin "2") (pinfunction "2_2") (pintype "passive"))
      (node (ref "R278") (pin "2") (pinfunction "2_2") (pintype "passive"))
    )
    (net (code "37") (name "Net-(C340-Pad1)") (class "Default")
      (node (ref "C340") (pin "1") (pinfunction "1_1") (pintype "passive"))
      (node (ref "R279") (pin "2") (pinfunction "2_2") (pintype "passive"))
      (node (ref "R280") (pin "2") (pinfunction "2_2") (pintype "passive"))
    )
    (net (code "38") (name "Net-(D10-K)") (class "Default")
      (node (ref "D10") (pin "1") (pinfunction "K_1") (pintype "passive"))
      (node (ref "R290") (pin "1") (pinfunction "1_1") (pintype "passive"))
    )
    (net (code "39") (name "Net-(D11-K)") (class "Default")
      (node (ref "D11") (pin "1") (pinfunction "K_1") (pintype "passive"))
      (node (ref "R291") (pin "1") (pinfunction "1_1") (pintype "passive"))
    )
    (net (code "40") (name "Net-(D12-K)") (class "Default")
      (node (ref "D12") (pin "1") (pinfunction "K_1") (pintype "passive"))
      (node (ref "R292") (pin "1") (pinfunction "1_1") (pintype "passive"))
    )
    (net (code "41") (name "Net-(D13-K)") (class "Default")
      (node (ref "D13") (pin "1") (pinfunction "K_1") (pintype "passive"))
      (node (ref "R294") (pin "1") (pinfunction "1_1") (pintype "passive"))
    )
    (net (code "42") (name "Net-(D14-K)") (class "Default")
      (node (ref "D14") (pin "1") (pinfunction "K_1") (pintype "passive"))
      (node (ref "R296") (pin "1") (pinfunction "1_1") (pintype "passive"))
    )
    (net (code "43") (name "Net-(U20A-RSET)") (class "Default")
      (node (ref "R289") (pin "1") (pinfunction "1_1") (pintype "passive"))
      (node (ref "U20") (pin "B14") (pinfunction "RSET_B14") (pintype "input"))
    )
    (net (code "44") (name "Net-(U20A-TRSTn)") (class "Default")
      (node (ref "R288") (pin "1") (pinfunction "1_1") (pintype "passive"))
      (node (ref "U20") (pin "A25") (pinfunction "TRSTn_A25") (pintype "input"))
    )
    (net (code "45") (name "Net-(U20A-TXD0{slash}TD0)") (class "Default")
      (node (ref "R281") (pin "2") (pinfunction "2_2") (pintype "passive"))
      (node (ref "U20") (pin "A6") (pinfunction "TXD0/TD0_A6") (pintype "input"))
      (node (ref "U20") (pin "B6") (pinfunction "TXD1/TD1_B6") (pintype "input"))
      (node (ref "U20") (pin "B7") (pinfunction "TXD2/TD2_B7") (pintype "input"))
      (node (ref "U20") (pin "B8") (pinfunction "TXD3/TD3_B8") (pintype "input"))
    )
    (net (code "46") (name "Net-(U20A-TXD4)") (class "Default")
      (node (ref "R282") (pin "2") (pinfunction "2_2") (pintype "passive"))
      (node (ref "U20") (pin "A10") (pinfunction "TXD6_A10") (pintype "input"))
      (node (ref "U20") (pin "A9") (pinfunction "TXD4_A9") (pintype "input"))
      (node (ref "U20") (pin "B10") (pinfunction "TXD7_B10") (pintype "input"))
      (node (ref "U20") (pin "B9") (pinfunction "TXD5_B9") (pintype "input"))
    )
    (net (code "47") (name "Net-(U20A-XTAL1)") (class "Default")
      (node (ref "U20") (pin "A30") (pinfunction "XTAL1_A30") (pintype "input"))
      (node (ref "U21") (pin "3") (pinfunction "OUTPUT_3") (pintype "passive"))
    )
    (net (code "48") (name "Net-(U21-TRI-STATE)") (class "Default")
      (node (ref "R286") (pin "2") (pinfunction "2_2") (pintype "passive"))
      (node (ref "U21") (pin "1") (pinfunction "TRI-STATE_1") (pintype "passive"))
    )
    (net (code "49") (name "Net-(U22-ADJ)") (class "Default")
      (node (ref "R293") (pin "1") (pinfunction "1_1") (pintype "passive"))
      (node (ref "R295") (pin "2") (pinfunction "2_2") (pintype "passive"))
      (node (ref "U22") (pin "5") (pinfunction "ADJ_5") (pintype "input"))
    )
    (net (code "50") (name "unconnected-(U20A-125CLK-PadB11)") (class "Default")
      (node (ref "U20") (pin "B11") (pinfunction "125CLK_B11") (pintype "output"))
    )
    (net (code "51") (name "unconnected-(U20A-COL{slash}LPBK-PadA45)") (class "Default")
      (node (ref "U20") (pin "A45") (pinfunction "COL/LPBK_A45") (pintype "bidirectional"))
    )
    (net (code "52") (name "unconnected-(U20A-CRS{slash}COMMA-PadB39)") (class "Default")
      (node (ref "U20") (pin "B39") (pinfunction "CRS/COMMA_B39") (pintype "tri_state"))
    )
    (net (code "53") (name "unconnected-(U20A-GTX_CLK{slash}TBI_TXCLK{slash}TXC-PadB4)") (class "Default")
      (node (ref "U20") (pin "B4") (pinfunction "GTX_CLK/TBI_TXCLK/TXC_B4") (pintype "input"))
    )
    (net (code "54") (name "unconnected-(U20A-HSDAC+-PadA20)") (class "Default")
      (node (ref "U20") (pin "A20") (pinfunction "HSDAC+_A20") (pintype "passive"))
    )
    (net (code "55") (name "unconnected-(U20A-HSDAC--PadB18)") (class "Default")
      (node (ref "U20") (pin "B18") (pinfunction "HSDAC-_B18") (pintype "passive"))
    )
    (net (code "56") (name "unconnected-(U20A-LED_DUPLEX-PadB33)") (class "Default")
      (node (ref "U20") (pin "B33") (pinfunction "LED_DUPLEX_B33") (pintype "output"))
    )
    (net (code "57") (name "unconnected-(U20A-NC-PadA7)") (class "Default")
      (node (ref "U20") (pin "A7") (pinfunction "NC_A7") (pintype "passive"))
    )
    (net (code "58") (name "unconnected-(U20A-NC-PadA28)") (class "Default")
      (node (ref "U20") (pin "A28") (pinfunction "NC_A28") (pintype "passive"))
    )
    (net (code "59") (name "unconnected-(U20A-RXD0{slash}RD0-PadA51)") (class "Default")
      (node (ref "U20") (pin "A51") (pinfunction "RXD0/RD0_A51") (pintype "tri_state"))
    )
    (net (code "60") (name "unconnected-(U20A-RXD1{slash}RD1-PadB43)") (class "Default")
      (node (ref "U20") (pin "B43") (pinfunction "RXD1/RD1_B43") (pintype "tri_state"))
    )
    (net (code "61") (name "unconnected-(U20A-RXD2{slash}RD2-PadA50)") (class "Default")
      (node (ref "U20") (pin "A50") (pinfunction "RXD2/RD2_A50") (pintype "tri_state"))
    )
    (net (code "62") (name "unconnected-(U20A-RXD3{slash}RD3-PadA49)") (class "Default")
      (node (ref "U20") (pin "A49") (pinfunction "RXD3/RD3_A49") (pintype "tri_state"))
    )
    (net (code "63") (name "unconnected-(U20A-RXD4-PadB42)") (class "Default")
      (node (ref "U20") (pin "B42") (pinfunction "RXD4_B42") (pintype "tri_state"))
    )
    (net (code "64") (name "unconnected-(U20A-RXD5-PadA48)") (class "Default")
      (node (ref "U20") (pin "A48") (pinfunction "RXD5_A48") (pintype "tri_state"))
    )
    (net (code "65") (name "unconnected-(U20A-RXD6-PadA47)") (class "Default")
      (node (ref "U20") (pin "A47") (pinfunction "RXD6_A47") (pintype "tri_state"))
    )
    (net (code "66") (name "unconnected-(U20A-RXD7-PadB40)") (class "Default")
      (node (ref "U20") (pin "B40") (pinfunction "RXD7_B40") (pintype "tri_state"))
    )
    (net (code "67") (name "unconnected-(U20A-RX_CLK{slash}RCLK0{slash}RXC-PadB1)") (class "Default")
      (node (ref "U20") (pin "B1") (pinfunction "RX_CLK/RCLK0/RXC_B1") (pintype "tri_state"))
    )
    (net (code "68") (name "unconnected-(U20A-RX_DV{slash}RXD8{slash}RX_CTL{slash}RD4_RD9-PadB44)") (class "Default")
      (node (ref "U20") (pin "B44") (pinfunction "RX_DV/RXD8/RX_CTL/RD4_RD9_B44") (pintype "tri_state"))
    )
    (net (code "69") (name "unconnected-(U20A-RX_ER{slash}RXD9-PadA2)") (class "Default")
      (node (ref "U20") (pin "A2") (pinfunction "RX_ER/RXD9_A2") (pintype "tri_state"))
    )
    (net (code "70") (name "unconnected-(U20A-SEL_FREQ-PadB26)") (class "Default")
      (node (ref "U20") (pin "B26") (pinfunction "SEL_FREQ_B26") (pintype "input"))
    )
    (net (code "71") (name "unconnected-(U20A-S_CLK+{slash}SD+-PadA43)") (class "Default")
      (node (ref "U20") (pin "A43") (pinfunction "S_CLK+/SD+_A43") (pintype "bidirectional"))
    )
    (net (code "72") (name "unconnected-(U20A-S_CLK-{slash}SD--PadB37)") (class "Default")
      (node (ref "U20") (pin "B37") (pinfunction "S_CLK-/SD-_B37") (pintype "bidirectional"))
    )
    (net (code "73") (name "unconnected-(U20A-TCK-PadA26)") (class "Default")
      (node (ref "U20") (pin "A26") (pinfunction "TCK_A26") (pintype "input"))
    )
    (net (code "74") (name "unconnected-(U20A-TDI-PadB21)") (class "Default")
      (node (ref "U20") (pin "B21") (pinfunction "TDI_B21") (pintype "input"))
    )
    (net (code "75") (name "unconnected-(U20A-TDO-PadA27)") (class "Default")
      (node (ref "U20") (pin "A27") (pinfunction "TDO_A27") (pintype "output"))
    )
    (net (code "76") (name "unconnected-(U20A-TMS-PadB22)") (class "Default")
      (node (ref "U20") (pin "B22") (pinfunction "TMS_B22") (pintype "input"))
    )
    (net (code "77") (name "unconnected-(U20A-TX_CLK{slash}RCLK1-PadB2)") (class "Default")
      (node (ref "U20") (pin "B2") (pinfunction "TX_CLK/RCLK1_B2") (pintype "tri_state"))
    )
    (net (code "78") (name "unconnected-(U20A-TX_EN{slash}TXD8{slash}TX_CTL{slash}TD4_TD9-PadA5)") (class "Default")
      (node (ref "U20") (pin "A5") (pinfunction "TX_EN/TXD8/TX_CTL/TD4_TD9_A5") (pintype "input"))
    )
    (net (code "79") (name "unconnected-(U20A-TX_ER{slash}TXD9-PadA4)") (class "Default")
      (node (ref "U20") (pin "A4") (pinfunction "TX_ER/TXD9_A4") (pintype "input"))
    )
    (net (code "80") (name "unconnected-(U20A-XTAL2-PadB25)") (class "Default")
      (node (ref "U20") (pin "B25") (pinfunction "XTAL2_B25") (pintype "passive"))
    )
  )
)
